# ENC28J60Breakout_V02.net
KiCad netlist of a schematic drawn in EAGLE
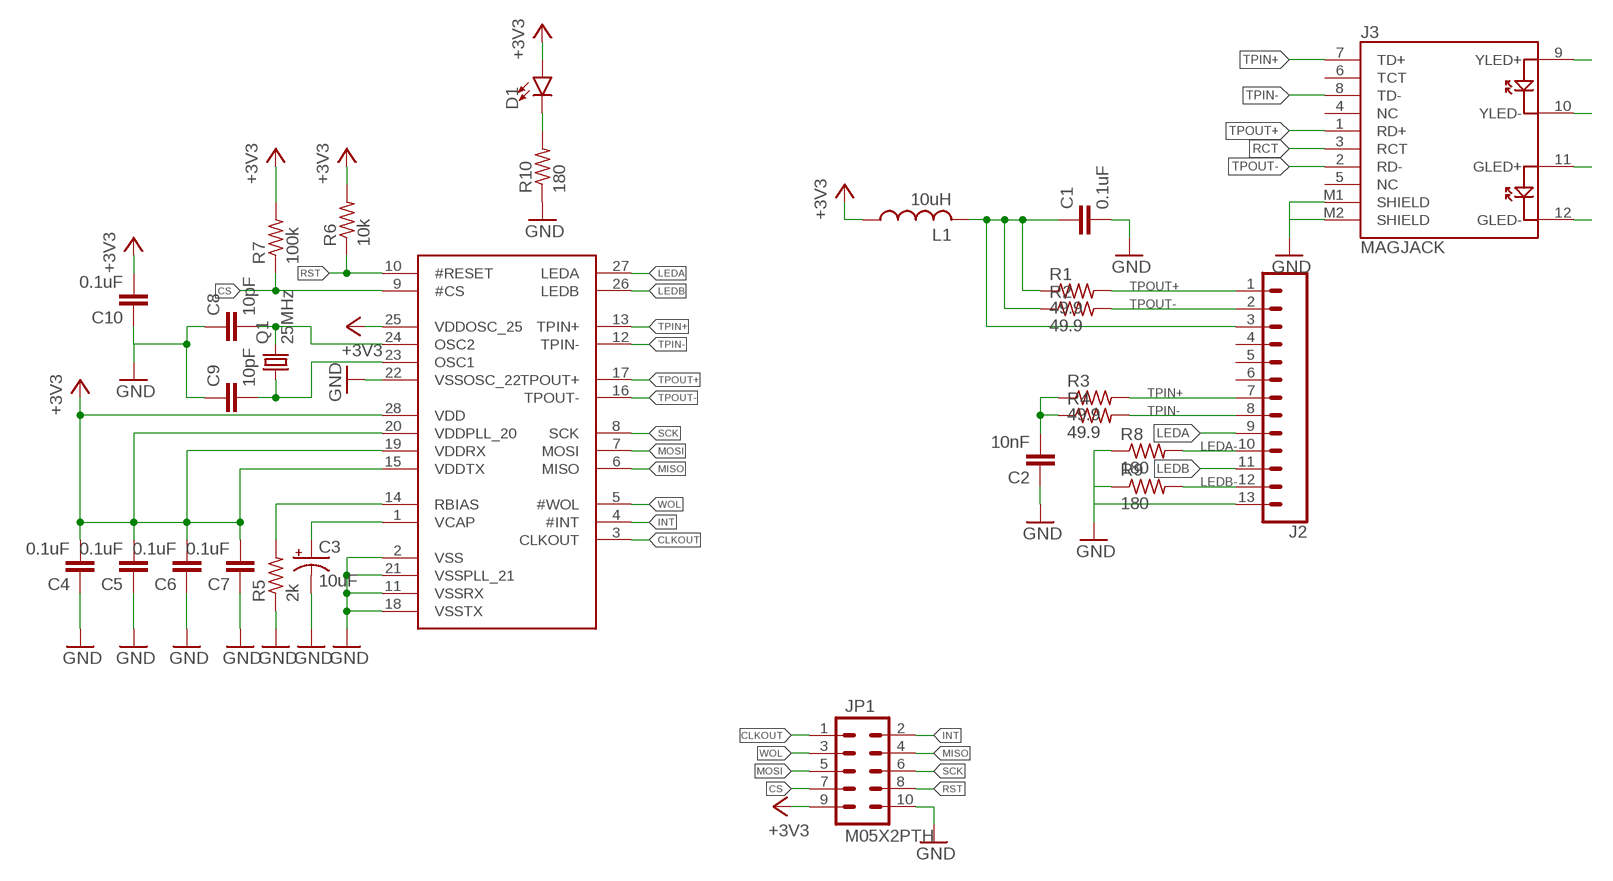
[diagram p0: schematic, sheet 1]

(export (version "E")
  (design (tool "Eeschema 10.0.6"))
  (components
    (comp (ref "C1")
      (value "0.1uF")
      (footprint "eagle-import:C050-024X044")
      (libsource (lib "eagle-import") (part "C-EU050-024X044"))
    )
    (comp (ref "C2")
      (value "10nF")
      (footprint "eagle-import:C050-024X044")
      (libsource (lib "eagle-import") (part "C-EU050-024X044"))
    )
    (comp (ref "C3")
      (value "10uF")
      (footprint "eagle-import:E2,5-7")
      (libsource (lib "eagle-import") (part "CPOL-USE2.5-7"))
    )
    (comp (ref "C4")
      (value "0.1uF")
      (footprint "eagle-import:C050-024X044")
      (libsource (lib "eagle-import") (part "C-EU050-024X044"))
    )
    (comp (ref "C5")
      (value "0.1uF")
      (footprint "eagle-import:C050-024X044")
      (libsource (lib "eagle-import") (part "C-EU050-024X044"))
    )
    (comp (ref "C6")
      (value "0.1uF")
      (footprint "eagle-import:C050-024X044")
      (libsource (lib "eagle-import") (part "C-EU050-024X044"))
    )
    (comp (ref "C7")
      (value "0.1uF")
      (footprint "eagle-import:C050-024X044")
      (libsource (lib "eagle-import") (part "C-EU050-024X044"))
    )
    (comp (ref "C8")
      (value "10pF")
      (footprint "eagle-import:C050-024X044")
      (libsource (lib "eagle-import") (part "C-EU050-024X044"))
    )
    (comp (ref "C9")
      (value "10pF")
      (footprint "eagle-import:C050-024X044")
      (libsource (lib "eagle-import") (part "C-EU050-024X044"))
    )
    (comp (ref "C10")
      (value "0.1uF")
      (footprint "eagle-import:C050-024X044")
      (libsource (lib "eagle-import") (part "C-EU050-024X044"))
    )
    (comp (ref "D1")
      (value "LED5MM")
      (footprint "eagle-import:LED_5MM")
      (libsource (lib "eagle-import") (part "LED5MM"))
    )
    (comp (ref "J2")
      (value "CONN_13")
      (footprint "eagle-import:1X13")
      (libsource (lib "eagle-import") (part "CONN_13"))
    )
    (comp (ref "J3")
      (value "MAGJACK")
      (footprint "eagle-import:MAGJACK")
      (libsource (lib "eagle-import") (part "MAGJACK"))
    )
    (comp (ref "JP1")
      (value "M05X2PTH")
      (footprint "eagle-import:AVR_ICSP")
      (libsource (lib "eagle-import") (part "M05X2PTH"))
    )
    (comp (ref "L1")
      (value "10uH")
      (footprint "eagle-import:0204_7")
      (libsource (lib "eagle-import") (part "L-US0204/7"))
    )
    (comp (ref "Q1")
      (value "25MHz")
      (footprint "eagle-import:HC49_S")
      (libsource (lib "eagle-import") (part "CRYSTALHC49S"))
    )
    (comp (ref "R1")
      (value "49.9")
      (footprint "eagle-import:0204_7")
      (libsource (lib "eagle-import") (part "R-US_0204/7"))
    )
    (comp (ref "R2")
      (value "49.9")
      (footprint "eagle-import:0204_7")
      (libsource (lib "eagle-import") (part "R-US_0204/7"))
    )
    (comp (ref "R3")
      (value "49.9")
      (footprint "eagle-import:0204_7")
      (libsource (lib "eagle-import") (part "R-US_0204/7"))
    )
    (comp (ref "R4")
      (value "49.9")
      (footprint "eagle-import:0204_7")
      (libsource (lib "eagle-import") (part "R-US_0204/7"))
    )
    (comp (ref "R5")
      (value "2k")
      (footprint "eagle-import:0204_7")
      (libsource (lib "eagle-import") (part "R-US_0204/7"))
    )
    (comp (ref "R6")
      (value "10k")
      (footprint "eagle-import:0204_7")
      (libsource (lib "eagle-import") (part "R-US_0204/7"))
    )
    (comp (ref "R7")
      (value "100k")
      (footprint "eagle-import:0204_7")
      (libsource (lib "eagle-import") (part "R-US_0204/7"))
    )
    (comp (ref "R8")
      (value "180")
      (footprint "eagle-import:0204_7")
      (libsource (lib "eagle-import") (part "R-US_0204/7"))
    )
    (comp (ref "R9")
      (value "180")
      (footprint "eagle-import:0204_7")
      (libsource (lib "eagle-import") (part "R-US_0204/7"))
    )
    (comp (ref "R10")
      (value "180")
      (footprint "eagle-import:0204_7")
      (libsource (lib "eagle-import") (part "R-US_0204/7"))
    )
    (comp (ref "U$1")
      (value "ENC28J60")
      (footprint "eagle-import:ENC28J60_DIP")
      (libsource (lib "eagle-import") (part "ENC28J60"))
    )
  )
  (nets
    (net (code "1") (name "+3V3") (class "Default")
      (node (ref "C10") (pin "2") (pinfunction "2_2") (pintype "passive"))
      (node (ref "C4") (pin "2") (pinfunction "2_2") (pintype "passive"))
      (node (ref "C5") (pin "2") (pinfunction "2_2") (pintype "passive"))
      (node (ref "C6") (pin "2") (pinfunction "2_2") (pintype "passive"))
      (node (ref "C7") (pin "2") (pinfunction "2_2") (pintype "passive"))
      (node (ref "D1") (pin "A") (pinfunction "A_A") (pintype "passive"))
      (node (ref "JP1") (pin "9") (pinfunction "9_9") (pintype "passive"))
      (node (ref "L1") (pin "1") (pinfunction "1_1") (pintype "passive"))
      (node (ref "R6") (pin "2") (pinfunction "2_2") (pintype "passive"))
      (node (ref "R7") (pin "2") (pinfunction "2_2") (pintype "passive"))
      (node (ref "U$1") (pin "15") (pinfunction "VDDTX_15") (pintype "bidirectional"))
      (node (ref "U$1") (pin "19") (pinfunction "VDDRX_19") (pintype "bidirectional"))
      (node (ref "U$1") (pin "20") (pinfunction "VDDPLL_20_20") (pintype "bidirectional"))
      (node (ref "U$1") (pin "25") (pinfunction "VDDOSC_25_25") (pintype "bidirectional"))
      (node (ref "U$1") (pin "28") (pinfunction "VDD_28") (pintype "bidirectional"))
    )
    (net (code "2") (name "/LEDA-") (class "Default")
      (node (ref "J2") (pin "10") (pinfunction "10_10") (pintype "passive"))
      (node (ref "J3") (pin "10") (pinfunction "YLED-_10") (pintype "bidirectional"))
      (node (ref "R8") (pin "2") (pinfunction "2_2") (pintype "passive"))
    )
    (net (code "3") (name "/LEDB-") (class "Default")
      (node (ref "J2") (pin "12") (pinfunction "12_12") (pintype "passive"))
      (node (ref "J3") (pin "12") (pinfunction "GLED-_12") (pintype "bidirectional"))
      (node (ref "R9") (pin "2") (pinfunction "2_2") (pintype "passive"))
    )
    (net (code "4") (name "CLKOUT") (class "Default")
      (node (ref "JP1") (pin "1") (pinfunction "1_1") (pintype "passive"))
      (node (ref "U$1") (pin "3") (pinfunction "CLKOUT_3") (pintype "bidirectional"))
    )
    (net (code "5") (name "CS") (class "Default")
      (node (ref "JP1") (pin "7") (pinfunction "7_7") (pintype "passive"))
      (node (ref "R7") (pin "1") (pinfunction "1_1") (pintype "passive"))
      (node (ref "U$1") (pin "9") (pinfunction "#CS_9") (pintype "bidirectional"))
    )
    (net (code "6") (name "GND") (class "Default")
      (node (ref "C1") (pin "2") (pinfunction "2_2") (pintype "passive"))
      (node (ref "C10") (pin "1") (pinfunction "1_1") (pintype "passive"))
      (node (ref "C2") (pin "1") (pinfunction "1_1") (pintype "passive"))
      (node (ref "C3") (pin "-") (pinfunction "-_-") (pintype "passive"))
      (node (ref "C4") (pin "1") (pinfunction "1_1") (pintype "passive"))
      (node (ref "C5") (pin "1") (pinfunction "1_1") (pintype "passive"))
      (node (ref "C6") (pin "1") (pinfunction "1_1") (pintype "passive"))
      (node (ref "C7") (pin "1") (pinfunction "1_1") (pintype "passive"))
      (node (ref "C8") (pin "1") (pinfunction "1_1") (pintype "passive"))
      (node (ref "C9") (pin "1") (pinfunction "1_1") (pintype "passive"))
      (node (ref "J2") (pin "13") (pinfunction "13_13") (pintype "passive"))
      (node (ref "J3") (pin "M1") (pinfunction "SHIELD_M1") (pintype "bidirectional"))
      (node (ref "J3") (pin "M2") (pinfunction "SHIELD_M2") (pintype "bidirectional"))
      (node (ref "JP1") (pin "10") (pinfunction "10_10") (pintype "passive"))
      (node (ref "R10") (pin "1") (pinfunction "1_1") (pintype "passive"))
      (node (ref "R5") (pin "1") (pinfunction "1_1") (pintype "passive"))
      (node (ref "R8") (pin "1") (pinfunction "1_1") (pintype "passive"))
      (node (ref "R9") (pin "1") (pinfunction "1_1") (pintype "passive"))
      (node (ref "U$1") (pin "11") (pinfunction "VSSRX_11") (pintype "bidirectional"))
      (node (ref "U$1") (pin "18") (pinfunction "VSSTX_18") (pintype "bidirectional"))
      (node (ref "U$1") (pin "2") (pinfunction "VSS_2") (pintype "bidirectional"))
      (node (ref "U$1") (pin "21") (pinfunction "VSSPLL_21_21") (pintype "bidirectional"))
      (node (ref "U$1") (pin "22") (pinfunction "VSSOSC_22_22") (pintype "bidirectional"))
    )
    (net (code "7") (name "INT") (class "Default")
      (node (ref "JP1") (pin "2") (pinfunction "2_2") (pintype "passive"))
      (node (ref "U$1") (pin "4") (pinfunction "#INT_4") (pintype "bidirectional"))
    )
    (net (code "8") (name "LEDA") (class "Default")
      (node (ref "J2") (pin "9") (pinfunction "9_9") (pintype "passive"))
      (node (ref "J3") (pin "9") (pinfunction "YLED+_9") (pintype "bidirectional"))
      (node (ref "U$1") (pin "27") (pinfunction "LEDA_27") (pintype "bidirectional"))
    )
    (net (code "9") (name "LEDB") (class "Default")
      (node (ref "J2") (pin "11") (pinfunction "11_11") (pintype "passive"))
      (node (ref "J3") (pin "11") (pinfunction "GLED+_11") (pintype "bidirectional"))
      (node (ref "U$1") (pin "26") (pinfunction "LEDB_26") (pintype "bidirectional"))
    )
    (net (code "10") (name "MISO") (class "Default")
      (node (ref "JP1") (pin "4") (pinfunction "4_4") (pintype "passive"))
      (node (ref "U$1") (pin "6") (pinfunction "MISO_6") (pintype "bidirectional"))
    )
    (net (code "11") (name "MOSI") (class "Default")
      (node (ref "JP1") (pin "5") (pinfunction "5_5") (pintype "passive"))
      (node (ref "U$1") (pin "7") (pinfunction "MOSI_7") (pintype "bidirectional"))
    )
    (net (code "12") (name "Net-(C2-Pad2)") (class "Default")
      (node (ref "C2") (pin "2") (pinfunction "2_2") (pintype "passive"))
      (node (ref "R3") (pin "1") (pinfunction "1_1") (pintype "passive"))
      (node (ref "R4") (pin "1") (pinfunction "1_1") (pintype "passive"))
    )
    (net (code "13") (name "Net-(D1-C)") (class "Default")
      (node (ref "D1") (pin "K") (pinfunction "C_K") (pintype "passive"))
      (node (ref "R10") (pin "2") (pinfunction "2_2") (pintype "passive"))
    )
    (net (code "14") (name "Net-(U$1-OSC1)") (class "Default")
      (node (ref "C9") (pin "2") (pinfunction "2_2") (pintype "passive"))
      (node (ref "Q1") (pin "1") (pinfunction "1_1") (pintype "passive"))
      (node (ref "U$1") (pin "23") (pinfunction "OSC1_23") (pintype "bidirectional"))
    )
    (net (code "15") (name "Net-(U$1-OSC2)") (class "Default")
      (node (ref "C8") (pin "2") (pinfunction "2_2") (pintype "passive"))
      (node (ref "Q1") (pin "2") (pinfunction "2_2") (pintype "passive"))
      (node (ref "U$1") (pin "24") (pinfunction "OSC2_24") (pintype "bidirectional"))
    )
    (net (code "16") (name "Net-(U$1-RBIAS)") (class "Default")
      (node (ref "R5") (pin "2") (pinfunction "2_2") (pintype "passive"))
      (node (ref "U$1") (pin "14") (pinfunction "RBIAS_14") (pintype "bidirectional"))
    )
    (net (code "17") (name "Net-(U$1-VCAP)") (class "Default")
      (node (ref "C3") (pin "+") (pinfunction "+_+") (pintype "passive"))
      (node (ref "U$1") (pin "1") (pinfunction "VCAP_1") (pintype "bidirectional"))
    )
    (net (code "18") (name "RCT") (class "Default")
      (node (ref "C1") (pin "1") (pinfunction "1_1") (pintype "passive"))
      (node (ref "J2") (pin "3") (pinfunction "3_3") (pintype "passive"))
      (node (ref "J3") (pin "3") (pinfunction "RCT_3") (pintype "bidirectional"))
      (node (ref "L1") (pin "2") (pinfunction "2_2") (pintype "passive"))
      (node (ref "R1") (pin "1") (pinfunction "1_1") (pintype "passive"))
      (node (ref "R2") (pin "1") (pinfunction "1_1") (pintype "passive"))
    )
    (net (code "19") (name "RST") (class "Default")
      (node (ref "JP1") (pin "8") (pinfunction "8_8") (pintype "passive"))
      (node (ref "R6") (pin "1") (pinfunction "1_1") (pintype "passive"))
      (node (ref "U$1") (pin "10") (pinfunction "#RESET_10") (pintype "bidirectional"))
    )
    (net (code "20") (name "SCK") (class "Default")
      (node (ref "JP1") (pin "6") (pinfunction "6_6") (pintype "passive"))
      (node (ref "U$1") (pin "8") (pinfunction "SCK_8") (pintype "bidirectional"))
    )
    (net (code "21") (name "TPIN+") (class "Default")
      (node (ref "J2") (pin "7") (pinfunction "7_7") (pintype "passive"))
      (node (ref "J3") (pin "7") (pinfunction "TD+_7") (pintype "bidirectional"))
      (node (ref "R3") (pin "2") (pinfunction "2_2") (pintype "passive"))
      (node (ref "U$1") (pin "13") (pinfunction "TPIN+_13") (pintype "bidirectional"))
    )
    (net (code "22") (name "TPIN-") (class "Default")
      (node (ref "J2") (pin "8") (pinfunction "8_8") (pintype "passive"))
      (node (ref "J3") (pin "8") (pinfunction "TD-_8") (pintype "bidirectional"))
      (node (ref "R4") (pin "2") (pinfunction "2_2") (pintype "passive"))
      (node (ref "U$1") (pin "12") (pinfunction "TPIN-_12") (pintype "bidirectional"))
    )
    (net (code "23") (name "TPOUT+") (class "Default")
      (node (ref "J2") (pin "1") (pinfunction "1_1") (pintype "passive"))
      (node (ref "J3") (pin "1") (pinfunction "RD+_1") (pintype "bidirectional"))
      (node (ref "R1") (pin "2") (pinfunction "2_2") (pintype "passive"))
      (node (ref "U$1") (pin "17") (pinfunction "TPOUT+_17") (pintype "bidirectional"))
    )
    (net (code "24") (name "TPOUT-") (class "Default")
      (node (ref "J2") (pin "2") (pinfunction "2_2") (pintype "passive"))
      (node (ref "J3") (pin "2") (pinfunction "RD-_2") (pintype "bidirectional"))
      (node (ref "R2") (pin "2") (pinfunction "2_2") (pintype "passive"))
      (node (ref "U$1") (pin "16") (pinfunction "TPOUT-_16") (pintype "bidirectional"))
    )
    (net (code "25") (name "WOL") (class "Default")
      (node (ref "JP1") (pin "3") (pinfunction "3_3") (pintype "passive"))
      (node (ref "U$1") (pin "5") (pinfunction "#WOL_5") (pintype "bidirectional"))
    )
    (net (code "26") (name "unconnected-(J2-Pad4)") (class "Default")
      (node (ref "J2") (pin "4") (pinfunction "4_4") (pintype "passive"))
    )
    (net (code "27") (name "unconnected-(J2-Pad5)") (class "Default")
      (node (ref "J2") (pin "5") (pinfunction "5_5") (pintype "passive"))
    )
    (net (code "28") (name "unconnected-(J2-Pad6)") (class "Default")
      (node (ref "J2") (pin "6") (pinfunction "6_6") (pintype "passive"))
    )
    (net (code "29") (name "unconnected-(J3-NC-Pad4)") (class "Default")
      (node (ref "J3") (pin "4") (pinfunction "NC_4") (pintype "bidirectional"))
    )
    (net (code "30") (name "unconnected-(J3-NC-Pad5)") (class "Default")
      (node (ref "J3") (pin "5") (pinfunction "NC_5") (pintype "bidirectional"))
    )
    (net (code "31") (name "unconnected-(J3-TCT-Pad6)") (class "Default")
      (node (ref "J3") (pin "6") (pinfunction "TCT_6") (pintype "bidirectional"))
    )
  )
)
